# MicroMultimeter_BUZZER_Sch.net
KiCad netlist of a schematic drawn in Altium Designer
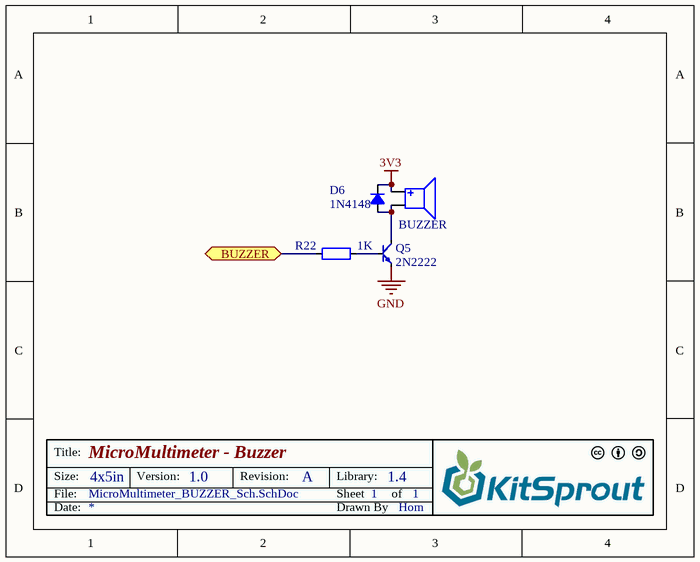
[diagram p0: MicroMultimeter_BUZZER_Sch.SchDoc]

(export (version "E")
  (design (tool "Eeschema 10.0.6"))
  (components
    (comp (ref "BUZZER")
      (value "Buzzer")
      (footprint "PCB_Module:Buzzer_5x5")
      (libsource (lib "SCH_Module") (part "Buzzer"))
    )
    (comp (ref "D6")
      (value "1N4148")
      (footprint "PCB_ActiveDIO:SOD323")
      (description "Diode")
      (fields (field (name "Comment") "Diode_SOD323"))
      (libsource (lib "SCH_Active") (part "Diode_SOD323"))
    )
    (comp (ref "Q5")
      (value "2N2222")
      (footprint "PCB_IntegratedCircuit:SOT23-3")
      (description "Transistor")
      (fields (field (name "Comment") "BJT_NPN"))
      (libsource (lib "SCH_Active") (part "BJT_NPN"))
    )
    (comp (ref "R22")
      (value "1K")
      (footprint "PCB_PassiveRes:RES_0603")
      (description "Resistor")
      (fields (field (name "Comment") "Res_0603"))
      (libsource (lib "SCH_Passive") (part "Res_0603"))
    )
  )
  (nets
    (net (code "1") (name "/BUZZER") (class "Default")
      (node (ref "R22") (pin "2") (pinfunction "2_2") (pintype "passive"))
    )
    (net (code "2") (name "3V3") (class "Default")
      (node (ref "BUZZER") (pin "P") (pinfunction "Positive_P") (pintype "passive"))
      (node (ref "D6") (pin "2") (pinfunction "K_2") (pintype "passive"))
    )
    (net (code "3") (name "GND") (class "Default")
      (node (ref "Q5") (pin "2") (pinfunction "E_2") (pintype "passive"))
    )
    (net (code "4") (name "Net-(BUZZER-Negative)") (class "Default")
      (node (ref "BUZZER") (pin "N") (pinfunction "Negative_N") (pintype "passive"))
      (node (ref "D6") (pin "1") (pinfunction "A_1") (pintype "passive"))
      (node (ref "Q5") (pin "3") (pinfunction "C_3") (pintype "passive"))
    )
    (net (code "5") (name "Net-(Q5-B)") (class "Default")
      (node (ref "Q5") (pin "1") (pinfunction "B_1") (pintype "passive"))
      (node (ref "R22") (pin "1") (pinfunction "1_1") (pintype "passive"))
    )
  )
)
